# 3-Displays.net
KiCad netlist of a schematic drawn in EAGLE
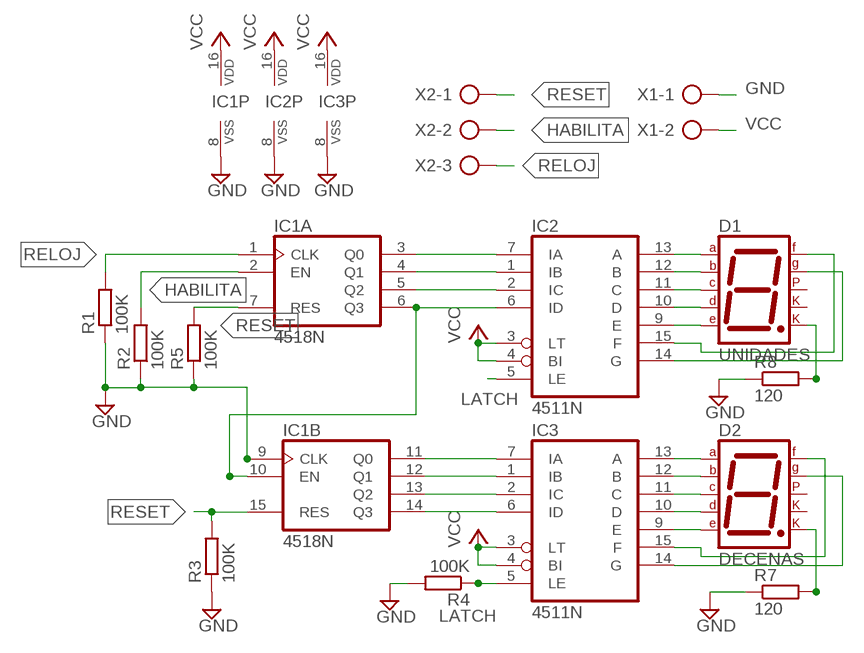
[diagram p0: schematic, sheet 1]

(export (version "E")
  (design (tool "Eeschema 10.0.6"))
  (components
    (comp (ref "D1")
      (value "UNIDADES")
      (footprint "eagle-import:7SEG-13")
      (libsource (lib "eagle-import") (part "7SEG-CK"))
    )
    (comp (ref "D2")
      (value "DECENAS")
      (footprint "eagle-import:7SEG-13")
      (libsource (lib "eagle-import") (part "7SEG-CK"))
    )
    (comp (ref "IC1")
      (value "4518N")
      (footprint "eagle-import:DIL16")
      (libsource (lib "eagle-import") (part "4518N"))
    )
    (comp (ref "IC2")
      (value "4511N")
      (footprint "eagle-import:DIL16")
      (libsource (lib "eagle-import") (part "4511N"))
    )
    (comp (ref "IC3")
      (value "4511N")
      (footprint "eagle-import:DIL16")
      (libsource (lib "eagle-import") (part "4511N"))
    )
    (comp (ref "R1")
      (value "100K")
      (footprint "eagle-import:0207_7")
      (libsource (lib "eagle-import") (part "R-EU_0207/7"))
    )
    (comp (ref "R2")
      (value "100K")
      (footprint "eagle-import:0207_7")
      (libsource (lib "eagle-import") (part "R-EU_0207/7"))
    )
    (comp (ref "R3")
      (value "100K")
      (footprint "eagle-import:0207_7")
      (libsource (lib "eagle-import") (part "R-EU_0207/7"))
    )
    (comp (ref "R4")
      (value "100K")
      (footprint "eagle-import:0207_7")
      (libsource (lib "eagle-import") (part "R-EU_0207/7"))
    )
    (comp (ref "R5")
      (value "100K")
      (footprint "eagle-import:0207_7")
      (libsource (lib "eagle-import") (part "R-EU_0207/7"))
    )
    (comp (ref "R7")
      (value "120")
      (footprint "eagle-import:0207_7")
      (libsource (lib "eagle-import") (part "R-EU_0207/7"))
    )
    (comp (ref "R8")
      (value "120")
      (footprint "eagle-import:0207_7")
      (libsource (lib "eagle-import") (part "R-EU_0207/7"))
    )
    (comp (ref "X1")
      (value "AK500/2-H")
      (footprint "eagle-import:AK500_2-H")
      (libsource (lib "eagle-import") (part "AK500/2-H"))
    )
    (comp (ref "X2")
      (value "AK500/3-H")
      (footprint "eagle-import:AK500_3-H")
      (libsource (lib "eagle-import") (part "AK500/3-H"))
    )
  )
  (nets
    (net (code "1") (name "/LATCH") (class "Default")
      (node (ref "IC2") (pin "5") (pinfunction "LE_5") (pintype "input"))
      (node (ref "IC3") (pin "5") (pinfunction "LE_5") (pintype "input"))
      (node (ref "R4") (pin "1") (pinfunction "1_1") (pintype "passive"))
    )
    (net (code "2") (name "GND") (class "Default")
      (node (ref "IC1") (pin "8") (pinfunction "VSS_8") (pintype "power_in"))
      (node (ref "IC1") (pin "9") (pinfunction "CLK_9") (pintype "input"))
      (node (ref "IC2") (pin "8") (pinfunction "VSS_8") (pintype "power_in"))
      (node (ref "IC3") (pin "8") (pinfunction "VSS_8") (pintype "power_in"))
      (node (ref "R1") (pin "1") (pinfunction "1_1") (pintype "passive"))
      (node (ref "R2") (pin "1") (pinfunction "1_1") (pintype "passive"))
      (node (ref "R3") (pin "1") (pinfunction "1_1") (pintype "passive"))
      (node (ref "R4") (pin "2") (pinfunction "2_2") (pintype "passive"))
      (node (ref "R5") (pin "1") (pinfunction "1_1") (pintype "passive"))
      (node (ref "R7") (pin "1") (pinfunction "1_1") (pintype "passive"))
      (node (ref "R8") (pin "1") (pinfunction "1_1") (pintype "passive"))
      (node (ref "X1") (pin "1") (pinfunction "KL_1") (pintype "passive"))
    )
    (net (code "3") (name "HABILITA") (class "Default")
      (node (ref "IC1") (pin "2") (pinfunction "EN_2") (pintype "input"))
      (node (ref "R2") (pin "2") (pinfunction "2_2") (pintype "passive"))
      (node (ref "X2") (pin "2") (pinfunction "KL_2") (pintype "passive"))
    )
    (net (code "4") (name "Net-(D1-A)") (class "Default")
      (node (ref "D1") (pin "7") (pinfunction "A_7") (pintype "passive"))
      (node (ref "IC2") (pin "13") (pinfunction "A_13") (pintype "output"))
    )
    (net (code "5") (name "Net-(D1-B)") (class "Default")
      (node (ref "D1") (pin "6") (pinfunction "B_6") (pintype "passive"))
      (node (ref "IC2") (pin "12") (pinfunction "B_12") (pintype "output"))
    )
    (net (code "6") (name "Net-(D1-C)") (class "Default")
      (node (ref "D1") (pin "4") (pinfunction "C_4") (pintype "passive"))
      (node (ref "IC2") (pin "11") (pinfunction "C_11") (pintype "output"))
    )
    (net (code "7") (name "Net-(D1-CK2)") (class "Default")
      (node (ref "D1") (pin "8") (pinfunction "CK2_8") (pintype "passive"))
      (node (ref "R8") (pin "2") (pinfunction "2_2") (pintype "passive"))
    )
    (net (code "8") (name "Net-(D1-D)") (class "Default")
      (node (ref "D1") (pin "2") (pinfunction "D_2") (pintype "passive"))
      (node (ref "IC2") (pin "10") (pinfunction "D_10") (pintype "output"))
    )
    (net (code "9") (name "Net-(D1-E)") (class "Default")
      (node (ref "D1") (pin "1") (pinfunction "E_1") (pintype "passive"))
      (node (ref "IC2") (pin "9") (pinfunction "E_9") (pintype "output"))
    )
    (net (code "10") (name "Net-(D1-F)") (class "Default")
      (node (ref "D1") (pin "9") (pinfunction "F_9") (pintype "passive"))
      (node (ref "IC2") (pin "15") (pinfunction "F_15") (pintype "output"))
    )
    (net (code "11") (name "Net-(D1-G)") (class "Default")
      (node (ref "D1") (pin "10") (pinfunction "G_10") (pintype "passive"))
      (node (ref "IC2") (pin "14") (pinfunction "G_14") (pintype "output"))
    )
    (net (code "12") (name "Net-(D2-A)") (class "Default")
      (node (ref "D2") (pin "7") (pinfunction "A_7") (pintype "passive"))
      (node (ref "IC3") (pin "13") (pinfunction "A_13") (pintype "output"))
    )
    (net (code "13") (name "Net-(D2-B)") (class "Default")
      (node (ref "D2") (pin "6") (pinfunction "B_6") (pintype "passive"))
      (node (ref "IC3") (pin "12") (pinfunction "B_12") (pintype "output"))
    )
    (net (code "14") (name "Net-(D2-C)") (class "Default")
      (node (ref "D2") (pin "4") (pinfunction "C_4") (pintype "passive"))
      (node (ref "IC3") (pin "11") (pinfunction "C_11") (pintype "output"))
    )
    (net (code "15") (name "Net-(D2-CK2)") (class "Default")
      (node (ref "D2") (pin "8") (pinfunction "CK2_8") (pintype "passive"))
      (node (ref "R7") (pin "2") (pinfunction "2_2") (pintype "passive"))
    )
    (net (code "16") (name "Net-(D2-D)") (class "Default")
      (node (ref "D2") (pin "2") (pinfunction "D_2") (pintype "passive"))
      (node (ref "IC3") (pin "10") (pinfunction "D_10") (pintype "output"))
    )
    (net (code "17") (name "Net-(D2-E)") (class "Default")
      (node (ref "D2") (pin "1") (pinfunction "E_1") (pintype "passive"))
      (node (ref "IC3") (pin "9") (pinfunction "E_9") (pintype "output"))
    )
    (net (code "18") (name "Net-(D2-F)") (class "Default")
      (node (ref "D2") (pin "9") (pinfunction "F_9") (pintype "passive"))
      (node (ref "IC3") (pin "15") (pinfunction "F_15") (pintype "output"))
    )
    (net (code "19") (name "Net-(D2-G)") (class "Default")
      (node (ref "D2") (pin "10") (pinfunction "G_10") (pintype "passive"))
      (node (ref "IC3") (pin "14") (pinfunction "G_14") (pintype "output"))
    )
    (net (code "20") (name "Net-(IC1A-Q0)") (class "Default")
      (node (ref "IC1") (pin "3") (pinfunction "Q0_3") (pintype "output"))
      (node (ref "IC2") (pin "7") (pinfunction "IA_7") (pintype "input"))
    )
    (net (code "21") (name "Net-(IC1A-Q1)") (class "Default")
      (node (ref "IC1") (pin "4") (pinfunction "Q1_4") (pintype "output"))
      (node (ref "IC2") (pin "1") (pinfunction "IB_1") (pintype "input"))
    )
    (net (code "22") (name "Net-(IC1A-Q2)") (class "Default")
      (node (ref "IC1") (pin "5") (pinfunction "Q2_5") (pintype "output"))
      (node (ref "IC2") (pin "2") (pinfunction "IC_2") (pintype "input"))
    )
    (net (code "23") (name "Net-(IC1A-Q3)") (class "Default")
      (node (ref "IC1") (pin "10") (pinfunction "EN_10") (pintype "input"))
      (node (ref "IC1") (pin "6") (pinfunction "Q3_6") (pintype "output"))
      (node (ref "IC2") (pin "6") (pinfunction "ID_6") (pintype "input"))
    )
    (net (code "24") (name "Net-(IC1B-Q0)") (class "Default")
      (node (ref "IC1") (pin "11") (pinfunction "Q0_11") (pintype "output"))
      (node (ref "IC3") (pin "7") (pinfunction "IA_7") (pintype "input"))
    )
    (net (code "25") (name "Net-(IC1B-Q1)") (class "Default")
      (node (ref "IC1") (pin "12") (pinfunction "Q1_12") (pintype "output"))
      (node (ref "IC3") (pin "1") (pinfunction "IB_1") (pintype "input"))
    )
    (net (code "26") (name "Net-(IC1B-Q2)") (class "Default")
      (node (ref "IC1") (pin "13") (pinfunction "Q2_13") (pintype "output"))
      (node (ref "IC3") (pin "2") (pinfunction "IC_2") (pintype "input"))
    )
    (net (code "27") (name "Net-(IC1B-Q3)") (class "Default")
      (node (ref "IC1") (pin "14") (pinfunction "Q3_14") (pintype "output"))
      (node (ref "IC3") (pin "6") (pinfunction "ID_6") (pintype "input"))
    )
    (net (code "28") (name "RELOJ") (class "Default")
      (node (ref "IC1") (pin "1") (pinfunction "CLK_1") (pintype "input"))
      (node (ref "R1") (pin "2") (pinfunction "2_2") (pintype "passive"))
      (node (ref "X2") (pin "3") (pinfunction "KL_3") (pintype "passive"))
    )
    (net (code "29") (name "RESET") (class "Default")
      (node (ref "IC1") (pin "15") (pinfunction "RES_15") (pintype "input"))
      (node (ref "IC1") (pin "7") (pinfunction "RES_7") (pintype "input"))
      (node (ref "R3") (pin "2") (pinfunction "2_2") (pintype "passive"))
      (node (ref "R5") (pin "2") (pinfunction "2_2") (pintype "passive"))
      (node (ref "X2") (pin "1") (pinfunction "KL_1") (pintype "passive"))
    )
    (net (code "30") (name "VCC") (class "Default")
      (node (ref "IC1") (pin "16") (pinfunction "VDD_16") (pintype "power_in"))
      (node (ref "IC2") (pin "16") (pinfunction "VDD_16") (pintype "power_in"))
      (node (ref "IC2") (pin "3") (pinfunction "LT_3") (pintype "input"))
      (node (ref "IC2") (pin "4") (pinfunction "BI_4") (pintype "input"))
      (node (ref "IC3") (pin "16") (pinfunction "VDD_16") (pintype "power_in"))
      (node (ref "IC3") (pin "3") (pinfunction "LT_3") (pintype "input"))
      (node (ref "IC3") (pin "4") (pinfunction "BI_4") (pintype "input"))
      (node (ref "X1") (pin "2") (pinfunction "KL_2") (pintype "passive"))
    )
    (net (code "31") (name "unconnected-(D1-CK1-Pad3)") (class "Default")
      (node (ref "D1") (pin "3") (pinfunction "CK1_3") (pintype "passive"))
    )
    (net (code "32") (name "unconnected-(D1-DP-Pad5)") (class "Default")
      (node (ref "D1") (pin "5") (pinfunction "DP_5") (pintype "passive"))
    )
    (net (code "33") (name "unconnected-(D2-CK1-Pad3)") (class "Default")
      (node (ref "D2") (pin "3") (pinfunction "CK1_3") (pintype "passive"))
    )
    (net (code "34") (name "unconnected-(D2-DP-Pad5)") (class "Default")
      (node (ref "D2") (pin "5") (pinfunction "DP_5") (pintype "passive"))
    )
  )
)
